# B136X.net
KiCad netlist of a schematic drawn in EAGLE
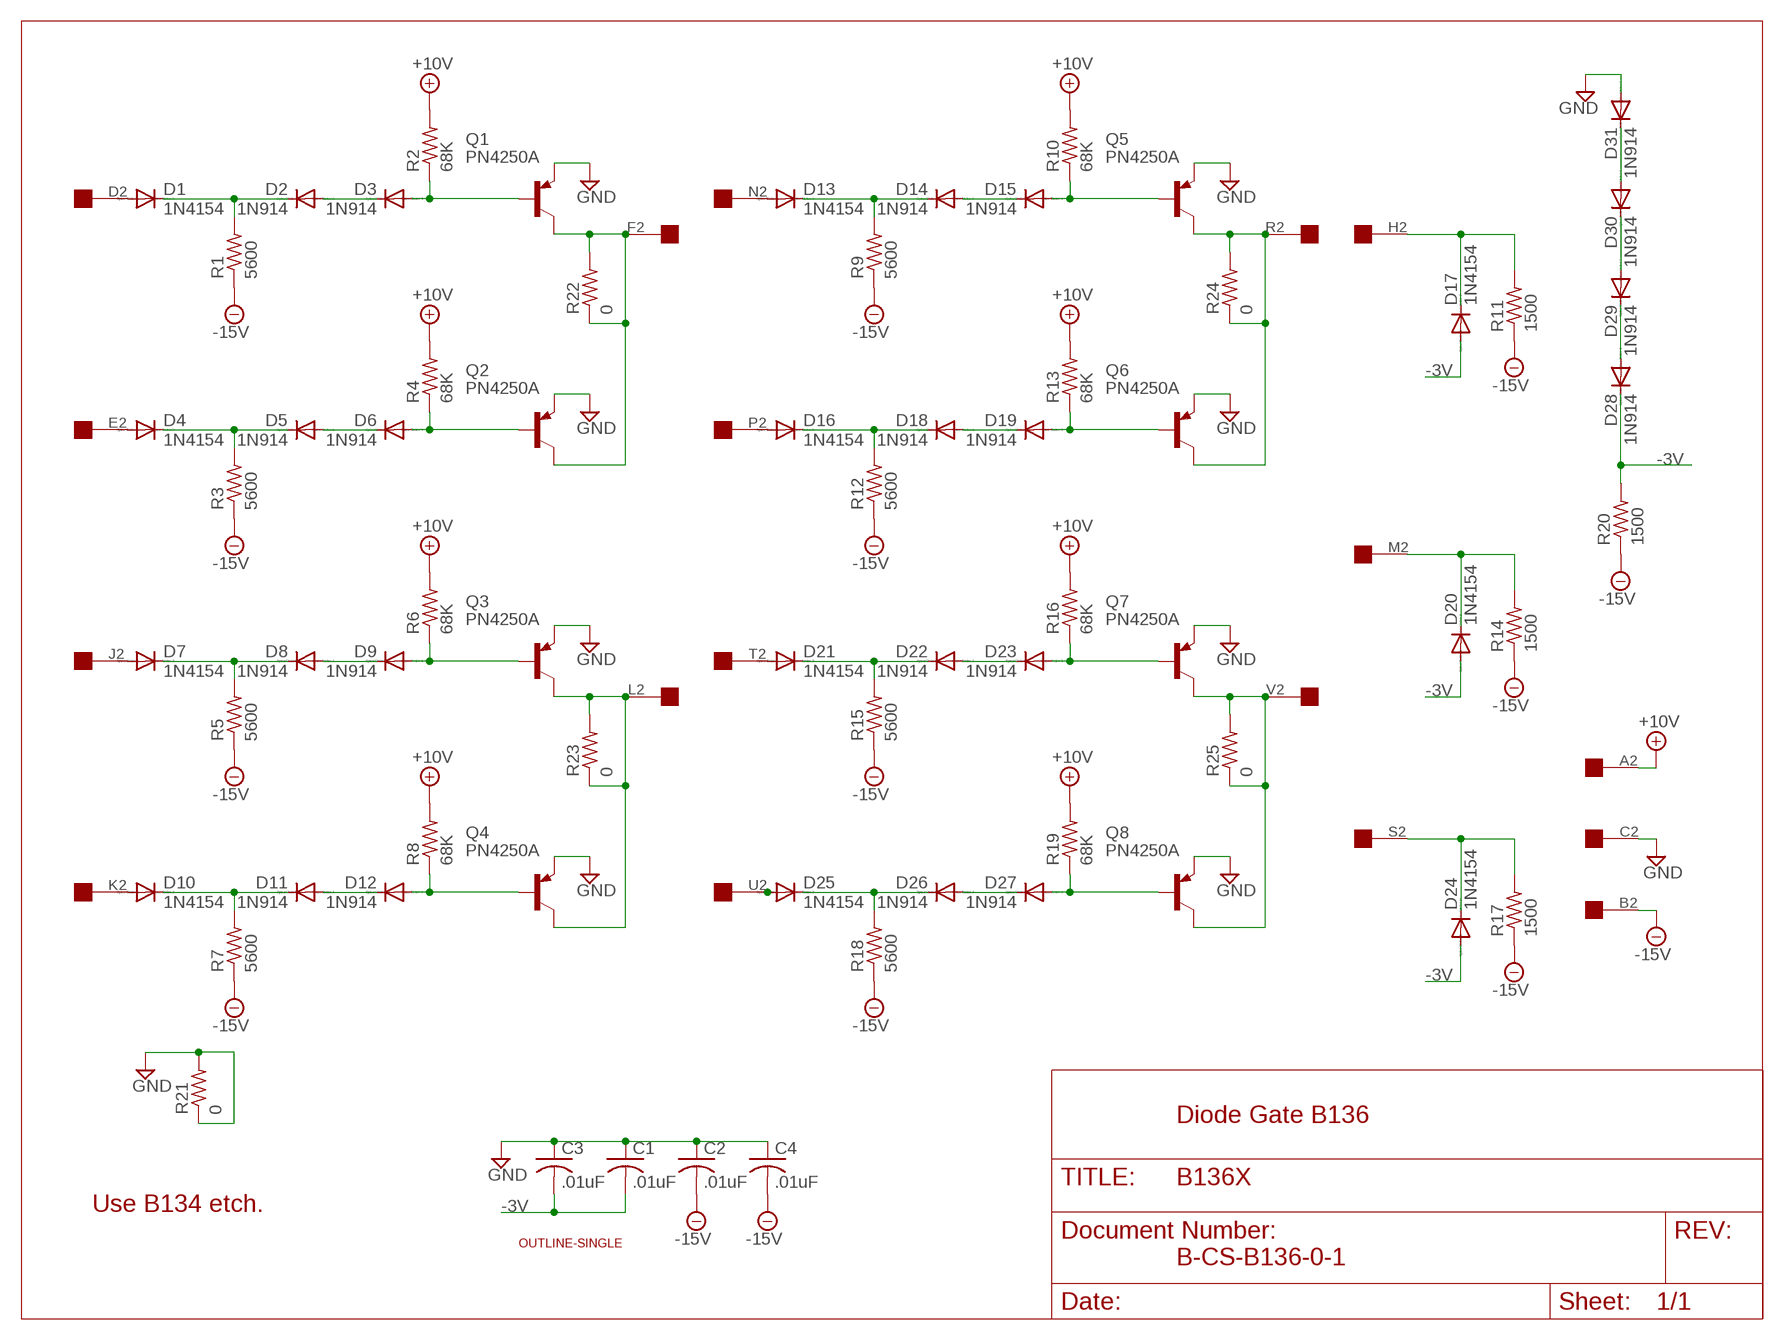
[diagram p0: schematic, sheet 1]

(export (version "E")
  (design (tool "Eeschema 10.0.6"))
  (components
    (comp (ref "C1")
      (value ".01uF")
      (footprint "eagle-import:C063-025X075")
      (libsource (lib "eagle-import") (part "C-US"))
    )
    (comp (ref "C2")
      (value ".01uF")
      (footprint "eagle-import:C063-025X075")
      (libsource (lib "eagle-import") (part "C-US"))
    )
    (comp (ref "C3")
      (value ".01uF")
      (footprint "eagle-import:C063-025X075")
      (libsource (lib "eagle-import") (part "C-US"))
    )
    (comp (ref "C4")
      (value ".01uF")
      (footprint "eagle-import:C063-025X075")
      (libsource (lib "eagle-import") (part "C-US"))
    )
    (comp (ref "D1")
      (value "1N4154")
      (footprint "eagle-import:DO35-10")
      (libsource (lib "eagle-import") (part "DIODE-DO35-10"))
    )
    (comp (ref "D2")
      (value "1N914")
      (footprint "eagle-import:DO35-10")
      (libsource (lib "eagle-import") (part "DIODE-DO35-10"))
    )
    (comp (ref "D3")
      (value "1N914")
      (footprint "eagle-import:DO35-10")
      (libsource (lib "eagle-import") (part "DIODE-DO35-10"))
    )
    (comp (ref "D4")
      (value "1N4154")
      (footprint "eagle-import:DO35-10")
      (libsource (lib "eagle-import") (part "DIODE-DO35-10"))
    )
    (comp (ref "D5")
      (value "1N914")
      (footprint "eagle-import:DO35-10")
      (libsource (lib "eagle-import") (part "DIODE-DO35-10"))
    )
    (comp (ref "D6")
      (value "1N914")
      (footprint "eagle-import:DO35-10")
      (libsource (lib "eagle-import") (part "DIODE-DO35-10"))
    )
    (comp (ref "D7")
      (value "1N4154")
      (footprint "eagle-import:DO35-10")
      (libsource (lib "eagle-import") (part "DIODE-DO35-10"))
    )
    (comp (ref "D8")
      (value "1N914")
      (footprint "eagle-import:DO35-10")
      (libsource (lib "eagle-import") (part "DIODE-DO35-10"))
    )
    (comp (ref "D9")
      (value "1N914")
      (footprint "eagle-import:DO35-10")
      (libsource (lib "eagle-import") (part "DIODE-DO35-10"))
    )
    (comp (ref "D10")
      (value "1N4154")
      (footprint "eagle-import:DO35-10")
      (libsource (lib "eagle-import") (part "DIODE-DO35-10"))
    )
    (comp (ref "D11")
      (value "1N914")
      (footprint "eagle-import:DO35-10")
      (libsource (lib "eagle-import") (part "DIODE-DO35-10"))
    )
    (comp (ref "D12")
      (value "1N914")
      (footprint "eagle-import:DO35-10")
      (libsource (lib "eagle-import") (part "DIODE-DO35-10"))
    )
    (comp (ref "D13")
      (value "1N4154")
      (footprint "eagle-import:DO35-10")
      (libsource (lib "eagle-import") (part "DIODE-DO35-10"))
    )
    (comp (ref "D14")
      (value "1N914")
      (footprint "eagle-import:DO35-10")
      (libsource (lib "eagle-import") (part "DIODE-DO35-10"))
    )
    (comp (ref "D15")
      (value "1N914")
      (footprint "eagle-import:DO35-10")
      (libsource (lib "eagle-import") (part "DIODE-DO35-10"))
    )
    (comp (ref "D16")
      (value "1N4154")
      (footprint "eagle-import:DO35-10")
      (libsource (lib "eagle-import") (part "DIODE-DO35-10"))
    )
    (comp (ref "D17")
      (value "1N4154")
      (footprint "eagle-import:DO35-10")
      (libsource (lib "eagle-import") (part "DIODE-DO35-10"))
    )
    (comp (ref "D18")
      (value "1N914")
      (footprint "eagle-import:DO35-10")
      (libsource (lib "eagle-import") (part "DIODE-DO35-10"))
    )
    (comp (ref "D19")
      (value "1N914")
      (footprint "eagle-import:DO35-10")
      (libsource (lib "eagle-import") (part "DIODE-DO35-10"))
    )
    (comp (ref "D20")
      (value "1N4154")
      (footprint "eagle-import:DO35-10")
      (libsource (lib "eagle-import") (part "DIODE-DO35-10"))
    )
    (comp (ref "D21")
      (value "1N4154")
      (footprint "eagle-import:DO35-10")
      (libsource (lib "eagle-import") (part "DIODE-DO35-10"))
    )
    (comp (ref "D22")
      (value "1N914")
      (footprint "eagle-import:DO35-10")
      (libsource (lib "eagle-import") (part "DIODE-DO35-10"))
    )
    (comp (ref "D23")
      (value "1N914")
      (footprint "eagle-import:DO35-10")
      (libsource (lib "eagle-import") (part "DIODE-DO35-10"))
    )
    (comp (ref "D24")
      (value "1N4154")
      (footprint "eagle-import:DO35-10")
      (libsource (lib "eagle-import") (part "DIODE-DO35-10"))
    )
    (comp (ref "D25")
      (value "1N4154")
      (footprint "eagle-import:DO35-10")
      (libsource (lib "eagle-import") (part "DIODE-DO35-10"))
    )
    (comp (ref "D26")
      (value "1N914")
      (footprint "eagle-import:DO35-10")
      (libsource (lib "eagle-import") (part "DIODE-DO35-10"))
    )
    (comp (ref "D27")
      (value "1N914")
      (footprint "eagle-import:DO35-10")
      (libsource (lib "eagle-import") (part "DIODE-DO35-10"))
    )
    (comp (ref "D28")
      (value "1N914")
      (footprint "eagle-import:DO35-10")
      (libsource (lib "eagle-import") (part "DIODE-DO35-10"))
    )
    (comp (ref "D29")
      (value "1N914")
      (footprint "eagle-import:DO35-10")
      (libsource (lib "eagle-import") (part "DIODE-DO35-10"))
    )
    (comp (ref "D30")
      (value "1N914")
      (footprint "eagle-import:DO35-10")
      (libsource (lib "eagle-import") (part "DIODE-DO35-10"))
    )
    (comp (ref "D31")
      (value "1N914")
      (footprint "eagle-import:DO35-10")
      (libsource (lib "eagle-import") (part "DIODE-DO35-10"))
    )
    (comp (ref "Q1")
      (value "PN4250A")
      (footprint "eagle-import:TO5")
      (libsource (lib "eagle-import") (part "-PNP-TO5"))
    )
    (comp (ref "Q2")
      (value "PN4250A")
      (footprint "eagle-import:TO5")
      (libsource (lib "eagle-import") (part "-PNP-TO5"))
    )
    (comp (ref "Q3")
      (value "PN4250A")
      (footprint "eagle-import:TO5")
      (libsource (lib "eagle-import") (part "-PNP-TO5"))
    )
    (comp (ref "Q4")
      (value "PN4250A")
      (footprint "eagle-import:TO5")
      (libsource (lib "eagle-import") (part "-PNP-TO5"))
    )
    (comp (ref "Q5")
      (value "PN4250A")
      (footprint "eagle-import:TO5")
      (libsource (lib "eagle-import") (part "-PNP-TO5"))
    )
    (comp (ref "Q6")
      (value "PN4250A")
      (footprint "eagle-import:TO5")
      (libsource (lib "eagle-import") (part "-PNP-TO5"))
    )
    (comp (ref "Q7")
      (value "PN4250A")
      (footprint "eagle-import:TO5")
      (libsource (lib "eagle-import") (part "-PNP-TO5"))
    )
    (comp (ref "Q8")
      (value "PN4250A")
      (footprint "eagle-import:TO5")
      (libsource (lib "eagle-import") (part "-PNP-TO5"))
    )
    (comp (ref "R1")
      (value "5600")
      (footprint "eagle-import:0207_10")
      (libsource (lib "eagle-import") (part "R-US_0207/10"))
    )
    (comp (ref "R2")
      (value "68K")
      (footprint "eagle-import:0207_10")
      (libsource (lib "eagle-import") (part "R-US_0207/10"))
    )
    (comp (ref "R3")
      (value "5600")
      (footprint "eagle-import:0207_10")
      (libsource (lib "eagle-import") (part "R-US_0207/10"))
    )
    (comp (ref "R4")
      (value "68K")
      (footprint "eagle-import:0207_10")
      (libsource (lib "eagle-import") (part "R-US_0207/10"))
    )
    (comp (ref "R5")
      (value "5600")
      (footprint "eagle-import:0207_10")
      (libsource (lib "eagle-import") (part "R-US_0207/10"))
    )
    (comp (ref "R6")
      (value "68K")
      (footprint "eagle-import:0207_10")
      (libsource (lib "eagle-import") (part "R-US_0207/10"))
    )
    (comp (ref "R7")
      (value "5600")
      (footprint "eagle-import:0207_10")
      (libsource (lib "eagle-import") (part "R-US_0207/10"))
    )
    (comp (ref "R8")
      (value "68K")
      (footprint "eagle-import:0207_10")
      (libsource (lib "eagle-import") (part "R-US_0207/10"))
    )
    (comp (ref "R9")
      (value "5600")
      (footprint "eagle-import:0207_10")
      (libsource (lib "eagle-import") (part "R-US_0207/10"))
    )
    (comp (ref "R10")
      (value "68K")
      (footprint "eagle-import:0207_10")
      (libsource (lib "eagle-import") (part "R-US_0207/10"))
    )
    (comp (ref "R11")
      (value "1500")
      (footprint "eagle-import:0207_10")
      (libsource (lib "eagle-import") (part "R-US_0207/10"))
    )
    (comp (ref "R12")
      (value "5600")
      (footprint "eagle-import:0207_10")
      (libsource (lib "eagle-import") (part "R-US_0207/10"))
    )
    (comp (ref "R13")
      (value "68K")
      (footprint "eagle-import:0207_10")
      (libsource (lib "eagle-import") (part "R-US_0207/10"))
    )
    (comp (ref "R14")
      (value "1500")
      (footprint "eagle-import:0207_10")
      (libsource (lib "eagle-import") (part "R-US_0207/10"))
    )
    (comp (ref "R15")
      (value "5600")
      (footprint "eagle-import:0207_10")
      (libsource (lib "eagle-import") (part "R-US_0207/10"))
    )
    (comp (ref "R16")
      (value "68K")
      (footprint "eagle-import:0207_10")
      (libsource (lib "eagle-import") (part "R-US_0207/10"))
    )
    (comp (ref "R17")
      (value "1500")
      (footprint "eagle-import:0207_10")
      (libsource (lib "eagle-import") (part "R-US_0207/10"))
    )
    (comp (ref "R18")
      (value "5600")
      (footprint "eagle-import:0207_10")
      (libsource (lib "eagle-import") (part "R-US_0207/10"))
    )
    (comp (ref "R19")
      (value "68K")
      (footprint "eagle-import:0207_10")
      (libsource (lib "eagle-import") (part "R-US_0207/10"))
    )
    (comp (ref "R20")
      (value "1500")
      (footprint "eagle-import:0207_10")
      (libsource (lib "eagle-import") (part "R-US_0207/10"))
    )
    (comp (ref "R21")
      (value "0")
      (footprint "eagle-import:0207_10")
      (libsource (lib "eagle-import") (part "R-US_0207/10"))
    )
    (comp (ref "R22")
      (value "0")
      (footprint "eagle-import:0207_10")
      (libsource (lib "eagle-import") (part "R-US_0207/10"))
    )
    (comp (ref "R23")
      (value "0")
      (footprint "eagle-import:0207_10")
      (libsource (lib "eagle-import") (part "R-US_0207/10"))
    )
    (comp (ref "R24")
      (value "0")
      (footprint "eagle-import:0207_10")
      (libsource (lib "eagle-import") (part "R-US_0207/10"))
    )
    (comp (ref "R25")
      (value "0")
      (footprint "eagle-import:0207_10")
      (libsource (lib "eagle-import") (part "R-US_0207/10"))
    )
    (comp (ref "U$1")
      (value "OUTLINE-SINGLE")
      (footprint "eagle-import:SINGLE")
      (libsource (lib "eagle-import") (part "OUTLINE-SINGLE"))
    )
    (comp (ref "U$2")
      (value "EDGE-1")
      (footprint "eagle-import:EDGE-CON1")
      (libsource (lib "eagle-import") (part "EDGE-1"))
    )
  )
  (nets
    (net (code "1") (name "+10V") (class "Default")
      (node (ref "R10") (pin "2") (pinfunction "2_2") (pintype "passive"))
      (node (ref "R13") (pin "2") (pinfunction "2_2") (pintype "passive"))
      (node (ref "R16") (pin "2") (pinfunction "2_2") (pintype "passive"))
      (node (ref "R19") (pin "2") (pinfunction "2_2") (pintype "passive"))
      (node (ref "R2") (pin "2") (pinfunction "2_2") (pintype "passive"))
      (node (ref "R4") (pin "2") (pinfunction "2_2") (pintype "passive"))
      (node (ref "R6") (pin "2") (pinfunction "2_2") (pintype "passive"))
      (node (ref "R8") (pin "2") (pinfunction "2_2") (pintype "passive"))
      (node (ref "U$2") (pin "A2") (pinfunction "1_A2") (pintype "bidirectional"))
    )
    (net (code "2") (name "-15V") (class "Default")
      (node (ref "C2") (pin "2") (pinfunction "2_2") (pintype "passive"))
      (node (ref "C4") (pin "2") (pinfunction "2_2") (pintype "passive"))
      (node (ref "R1") (pin "1") (pinfunction "1_1") (pintype "passive"))
      (node (ref "R11") (pin "1") (pinfunction "1_1") (pintype "passive"))
      (node (ref "R12") (pin "1") (pinfunction "1_1") (pintype "passive"))
      (node (ref "R14") (pin "1") (pinfunction "1_1") (pintype "passive"))
      (node (ref "R15") (pin "1") (pinfunction "1_1") (pintype "passive"))
      (node (ref "R17") (pin "1") (pinfunction "1_1") (pintype "passive"))
      (node (ref "R18") (pin "1") (pinfunction "1_1") (pintype "passive"))
      (node (ref "R20") (pin "1") (pinfunction "1_1") (pintype "passive"))
      (node (ref "R3") (pin "1") (pinfunction "1_1") (pintype "passive"))
      (node (ref "R5") (pin "1") (pinfunction "1_1") (pintype "passive"))
      (node (ref "R7") (pin "1") (pinfunction "1_1") (pintype "passive"))
      (node (ref "R9") (pin "1") (pinfunction "1_1") (pintype "passive"))
      (node (ref "U$2") (pin "B2") (pinfunction "1_B2") (pintype "bidirectional"))
    )
    (net (code "3") (name "/-3V") (class "Default")
      (node (ref "C1") (pin "2") (pinfunction "2_2") (pintype "passive"))
      (node (ref "C3") (pin "2") (pinfunction "2_2") (pintype "passive"))
      (node (ref "D17") (pin "A") (pinfunction "A_A") (pintype "passive"))
      (node (ref "D20") (pin "A") (pinfunction "A_A") (pintype "passive"))
      (node (ref "D24") (pin "A") (pinfunction "A_A") (pintype "passive"))
      (node (ref "D28") (pin "C") (pinfunction "C_C") (pintype "passive"))
      (node (ref "R20") (pin "2") (pinfunction "2_2") (pintype "passive"))
    )
    (net (code "4") (name "GND") (class "Default")
      (node (ref "C1") (pin "1") (pinfunction "1_1") (pintype "passive"))
      (node (ref "C2") (pin "1") (pinfunction "1_1") (pintype "passive"))
      (node (ref "C3") (pin "1") (pinfunction "1_1") (pintype "passive"))
      (node (ref "C4") (pin "1") (pinfunction "1_1") (pintype "passive"))
      (node (ref "D31") (pin "A") (pinfunction "A_A") (pintype "passive"))
      (node (ref "Q1") (pin "1") (pinfunction "E_1") (pintype "passive"))
      (node (ref "Q2") (pin "1") (pinfunction "E_1") (pintype "passive"))
      (node (ref "Q3") (pin "1") (pinfunction "E_1") (pintype "passive"))
      (node (ref "Q4") (pin "1") (pinfunction "E_1") (pintype "passive"))
      (node (ref "Q5") (pin "1") (pinfunction "E_1") (pintype "passive"))
      (node (ref "Q6") (pin "1") (pinfunction "E_1") (pintype "passive"))
      (node (ref "Q7") (pin "1") (pinfunction "E_1") (pintype "passive"))
      (node (ref "Q8") (pin "1") (pinfunction "E_1") (pintype "passive"))
      (node (ref "R21") (pin "1") (pinfunction "1_1") (pintype "passive"))
      (node (ref "R21") (pin "2") (pinfunction "2_2") (pintype "passive"))
      (node (ref "U$2") (pin "C2") (pinfunction "1_C2") (pintype "bidirectional"))
    )
    (net (code "5") (name "Net-(D1-PadC)") (class "Default")
      (node (ref "D1") (pin "C") (pinfunction "C_C") (pintype "passive"))
      (node (ref "D2") (pin "C") (pinfunction "C_C") (pintype "passive"))
      (node (ref "R1") (pin "2") (pinfunction "2_2") (pintype "passive"))
    )
    (net (code "6") (name "Net-(D2-PadA)") (class "Default")
      (node (ref "D2") (pin "A") (pinfunction "A_A") (pintype "passive"))
      (node (ref "D3") (pin "C") (pinfunction "C_C") (pintype "passive"))
    )
    (net (code "7") (name "Net-(D4-PadC)") (class "Default")
      (node (ref "D4") (pin "C") (pinfunction "C_C") (pintype "passive"))
      (node (ref "D5") (pin "C") (pinfunction "C_C") (pintype "passive"))
      (node (ref "R3") (pin "2") (pinfunction "2_2") (pintype "passive"))
    )
    (net (code "8") (name "Net-(D5-PadA)") (class "Default")
      (node (ref "D5") (pin "A") (pinfunction "A_A") (pintype "passive"))
      (node (ref "D6") (pin "C") (pinfunction "C_C") (pintype "passive"))
    )
    (net (code "9") (name "Net-(D7-PadC)") (class "Default")
      (node (ref "D7") (pin "C") (pinfunction "C_C") (pintype "passive"))
      (node (ref "D8") (pin "C") (pinfunction "C_C") (pintype "passive"))
      (node (ref "R5") (pin "2") (pinfunction "2_2") (pintype "passive"))
    )
    (net (code "10") (name "Net-(D8-PadA)") (class "Default")
      (node (ref "D8") (pin "A") (pinfunction "A_A") (pintype "passive"))
      (node (ref "D9") (pin "C") (pinfunction "C_C") (pintype "passive"))
    )
    (net (code "11") (name "Net-(D10-PadC)") (class "Default")
      (node (ref "D10") (pin "C") (pinfunction "C_C") (pintype "passive"))
      (node (ref "D11") (pin "C") (pinfunction "C_C") (pintype "passive"))
      (node (ref "R7") (pin "2") (pinfunction "2_2") (pintype "passive"))
    )
    (net (code "12") (name "Net-(D11-PadA)") (class "Default")
      (node (ref "D11") (pin "A") (pinfunction "A_A") (pintype "passive"))
      (node (ref "D12") (pin "C") (pinfunction "C_C") (pintype "passive"))
    )
    (net (code "13") (name "Net-(D13-PadC)") (class "Default")
      (node (ref "D13") (pin "C") (pinfunction "C_C") (pintype "passive"))
      (node (ref "D14") (pin "C") (pinfunction "C_C") (pintype "passive"))
      (node (ref "R9") (pin "2") (pinfunction "2_2") (pintype "passive"))
    )
    (net (code "14") (name "Net-(D14-PadA)") (class "Default")
      (node (ref "D14") (pin "A") (pinfunction "A_A") (pintype "passive"))
      (node (ref "D15") (pin "C") (pinfunction "C_C") (pintype "passive"))
    )
    (net (code "15") (name "Net-(D16-PadC)") (class "Default")
      (node (ref "D16") (pin "C") (pinfunction "C_C") (pintype "passive"))
      (node (ref "D18") (pin "C") (pinfunction "C_C") (pintype "passive"))
      (node (ref "R12") (pin "2") (pinfunction "2_2") (pintype "passive"))
    )
    (net (code "16") (name "Net-(D18-PadA)") (class "Default")
      (node (ref "D18") (pin "A") (pinfunction "A_A") (pintype "passive"))
      (node (ref "D19") (pin "C") (pinfunction "C_C") (pintype "passive"))
    )
    (net (code "17") (name "Net-(D21-PadC)") (class "Default")
      (node (ref "D21") (pin "C") (pinfunction "C_C") (pintype "passive"))
      (node (ref "D22") (pin "C") (pinfunction "C_C") (pintype "passive"))
      (node (ref "R15") (pin "2") (pinfunction "2_2") (pintype "passive"))
    )
    (net (code "18") (name "Net-(D22-PadA)") (class "Default")
      (node (ref "D22") (pin "A") (pinfunction "A_A") (pintype "passive"))
      (node (ref "D23") (pin "C") (pinfunction "C_C") (pintype "passive"))
    )
    (net (code "19") (name "Net-(D25-PadC)") (class "Default")
      (node (ref "D25") (pin "C") (pinfunction "C_C") (pintype "passive"))
      (node (ref "D26") (pin "C") (pinfunction "C_C") (pintype "passive"))
      (node (ref "R18") (pin "2") (pinfunction "2_2") (pintype "passive"))
    )
    (net (code "20") (name "Net-(D26-PadA)") (class "Default")
      (node (ref "D26") (pin "A") (pinfunction "A_A") (pintype "passive"))
      (node (ref "D27") (pin "C") (pinfunction "C_C") (pintype "passive"))
    )
    (net (code "21") (name "Net-(D28-PadA)") (class "Default")
      (node (ref "D28") (pin "A") (pinfunction "A_A") (pintype "passive"))
      (node (ref "D29") (pin "C") (pinfunction "C_C") (pintype "passive"))
    )
    (net (code "22") (name "Net-(D29-PadA)") (class "Default")
      (node (ref "D29") (pin "A") (pinfunction "A_A") (pintype "passive"))
      (node (ref "D30") (pin "C") (pinfunction "C_C") (pintype "passive"))
    )
    (net (code "23") (name "Net-(D30-PadA)") (class "Default")
      (node (ref "D30") (pin "A") (pinfunction "A_A") (pintype "passive"))
      (node (ref "D31") (pin "C") (pinfunction "C_C") (pintype "passive"))
    )
    (net (code "24") (name "Net-(Q1-B)") (class "Default")
      (node (ref "D3") (pin "A") (pinfunction "A_A") (pintype "passive"))
      (node (ref "Q1") (pin "2") (pinfunction "B_2") (pintype "passive"))
      (node (ref "R2") (pin "1") (pinfunction "1_1") (pintype "passive"))
    )
    (net (code "25") (name "Net-(Q1-C)") (class "Default")
      (node (ref "Q1") (pin "3") (pinfunction "C_3") (pintype "passive"))
      (node (ref "Q2") (pin "3") (pinfunction "C_3") (pintype "passive"))
      (node (ref "R22") (pin "1") (pinfunction "1_1") (pintype "passive"))
      (node (ref "R22") (pin "2") (pinfunction "2_2") (pintype "passive"))
      (node (ref "U$2") (pin "F2") (pinfunction "1_F2") (pintype "bidirectional"))
    )
    (net (code "26") (name "Net-(Q2-B)") (class "Default")
      (node (ref "D6") (pin "A") (pinfunction "A_A") (pintype "passive"))
      (node (ref "Q2") (pin "2") (pinfunction "B_2") (pintype "passive"))
      (node (ref "R4") (pin "1") (pinfunction "1_1") (pintype "passive"))
    )
    (net (code "27") (name "Net-(Q3-B)") (class "Default")
      (node (ref "D9") (pin "A") (pinfunction "A_A") (pintype "passive"))
      (node (ref "Q3") (pin "2") (pinfunction "B_2") (pintype "passive"))
      (node (ref "R6") (pin "1") (pinfunction "1_1") (pintype "passive"))
    )
    (net (code "28") (name "Net-(Q3-C)") (class "Default")
      (node (ref "Q3") (pin "3") (pinfunction "C_3") (pintype "passive"))
      (node (ref "Q4") (pin "3") (pinfunction "C_3") (pintype "passive"))
      (node (ref "R23") (pin "1") (pinfunction "1_1") (pintype "passive"))
      (node (ref "R23") (pin "2") (pinfunction "2_2") (pintype "passive"))
      (node (ref "U$2") (pin "L2") (pinfunction "1_L2") (pintype "bidirectional"))
    )
    (net (code "29") (name "Net-(Q4-B)") (class "Default")
      (node (ref "D12") (pin "A") (pinfunction "A_A") (pintype "passive"))
      (node (ref "Q4") (pin "2") (pinfunction "B_2") (pintype "passive"))
      (node (ref "R8") (pin "1") (pinfunction "1_1") (pintype "passive"))
    )
    (net (code "30") (name "Net-(Q5-B)") (class "Default")
      (node (ref "D15") (pin "A") (pinfunction "A_A") (pintype "passive"))
      (node (ref "Q5") (pin "2") (pinfunction "B_2") (pintype "passive"))
      (node (ref "R10") (pin "1") (pinfunction "1_1") (pintype "passive"))
    )
    (net (code "31") (name "Net-(Q5-C)") (class "Default")
      (node (ref "Q5") (pin "3") (pinfunction "C_3") (pintype "passive"))
      (node (ref "Q6") (pin "3") (pinfunction "C_3") (pintype "passive"))
      (node (ref "R24") (pin "1") (pinfunction "1_1") (pintype "passive"))
      (node (ref "R24") (pin "2") (pinfunction "2_2") (pintype "passive"))
      (node (ref "U$2") (pin "R2") (pinfunction "1_R2") (pintype "bidirectional"))
    )
    (net (code "32") (name "Net-(Q6-B)") (class "Default")
      (node (ref "D19") (pin "A") (pinfunction "A_A") (pintype "passive"))
      (node (ref "Q6") (pin "2") (pinfunction "B_2") (pintype "passive"))
      (node (ref "R13") (pin "1") (pinfunction "1_1") (pintype "passive"))
    )
    (net (code "33") (name "Net-(Q7-B)") (class "Default")
      (node (ref "D23") (pin "A") (pinfunction "A_A") (pintype "passive"))
      (node (ref "Q7") (pin "2") (pinfunction "B_2") (pintype "passive"))
      (node (ref "R16") (pin "1") (pinfunction "1_1") (pintype "passive"))
    )
    (net (code "34") (name "Net-(Q7-C)") (class "Default")
      (node (ref "Q7") (pin "3") (pinfunction "C_3") (pintype "passive"))
      (node (ref "Q8") (pin "3") (pinfunction "C_3") (pintype "passive"))
      (node (ref "R25") (pin "1") (pinfunction "1_1") (pintype "passive"))
      (node (ref "R25") (pin "2") (pinfunction "2_2") (pintype "passive"))
      (node (ref "U$2") (pin "V2") (pinfunction "1_V2") (pintype "bidirectional"))
    )
    (net (code "35") (name "Net-(Q8-B)") (class "Default")
      (node (ref "D27") (pin "A") (pinfunction "A_A") (pintype "passive"))
      (node (ref "Q8") (pin "2") (pinfunction "B_2") (pintype "passive"))
      (node (ref "R19") (pin "1") (pinfunction "1_1") (pintype "passive"))
    )
    (net (code "36") (name "Net-(U$2D-1)") (class "Default")
      (node (ref "D1") (pin "A") (pinfunction "A_A") (pintype "passive"))
      (node (ref "U$2") (pin "D2") (pinfunction "1_D2") (pintype "bidirectional"))
    )
    (net (code "37") (name "Net-(U$2E-1)") (class "Default")
      (node (ref "D4") (pin "A") (pinfunction "A_A") (pintype "passive"))
      (node (ref "U$2") (pin "E2") (pinfunction "1_E2") (pintype "bidirectional"))
    )
    (net (code "38") (name "Net-(U$2G-1)") (class "Default")
      (node (ref "D17") (pin "C") (pinfunction "C_C") (pintype "passive"))
      (node (ref "R11") (pin "2") (pinfunction "2_2") (pintype "passive"))
      (node (ref "U$2") (pin "H2") (pinfunction "1_H2") (pintype "bidirectional"))
    )
    (net (code "39") (name "Net-(U$2H-1)") (class "Default")
      (node (ref "D7") (pin "A") (pinfunction "A_A") (pintype "passive"))
      (node (ref "U$2") (pin "J2") (pinfunction "1_J2") (pintype "bidirectional"))
    )
    (net (code "40") (name "Net-(U$2I-1)") (class "Default")
      (node (ref "D10") (pin "A") (pinfunction "A_A") (pintype "passive"))
      (node (ref "U$2") (pin "K2") (pinfunction "1_K2") (pintype "bidirectional"))
    )
    (net (code "41") (name "Net-(U$2K-1)") (class "Default")
      (node (ref "D20") (pin "C") (pinfunction "C_C") (pintype "passive"))
      (node (ref "R14") (pin "2") (pinfunction "2_2") (pintype "passive"))
      (node (ref "U$2") (pin "M2") (pinfunction "1_M2") (pintype "bidirectional"))
    )
    (net (code "42") (name "Net-(U$2L-1)") (class "Default")
      (node (ref "D13") (pin "A") (pinfunction "A_A") (pintype "passive"))
      (node (ref "U$2") (pin "N2") (pinfunction "1_N2") (pintype "bidirectional"))
    )
    (net (code "43") (name "Net-(U$2M-1)") (class "Default")
      (node (ref "D16") (pin "A") (pinfunction "A_A") (pintype "passive"))
      (node (ref "U$2") (pin "P2") (pinfunction "1_P2") (pintype "bidirectional"))
    )
    (net (code "44") (name "Net-(U$2O-1)") (class "Default")
      (node (ref "D24") (pin "C") (pinfunction "C_C") (pintype "passive"))
      (node (ref "R17") (pin "2") (pinfunction "2_2") (pintype "passive"))
      (node (ref "U$2") (pin "S2") (pinfunction "1_S2") (pintype "bidirectional"))
    )
    (net (code "45") (name "Net-(U$2P-1)") (class "Default")
      (node (ref "D21") (pin "A") (pinfunction "A_A") (pintype "passive"))
      (node (ref "U$2") (pin "T2") (pinfunction "1_T2") (pintype "bidirectional"))
    )
    (net (code "46") (name "Net-(U$2Q-1)") (class "Default")
      (node (ref "D25") (pin "A") (pinfunction "A_A") (pintype "passive"))
      (node (ref "U$2") (pin "U2") (pinfunction "1_U2") (pintype "bidirectional"))
    )
  )
)
